# MCU_connector.net
KiCad netlist of a schematic drawn in Altium Designer
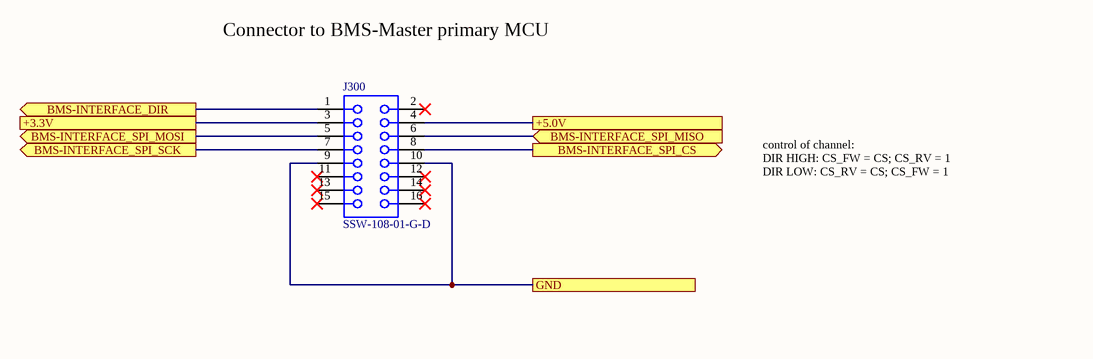
[diagram p0: MCU_connector.SchDoc]

(export (version "E")
  (design (tool "Eeschema 10.0.6"))
  (components
    (comp (ref "J300")
      (value "SSW-108-01-G-D")
      (footprint "SMTC-SSW-108-01-X-D")
      (description "SQ Post Socket, Through-hole, Vertical, -55 to 125 degC, 2.54mm Pitch, 16-Pin, Female, RoHS")
      (fields (field (name "MANUFACTURER") "Samtec"))
      (libsource (lib "Altium Content Vault") (part "SMTC-SSW-108-X-X-D-X"))
    )
  )
  (nets
    (net (code "1") (name "/+3.3V") (class "Default")
      (node (ref "J300") (pin "3") (pinfunction "3_3") (pintype "passive"))
    )
    (net (code "2") (name "/+5.0V") (class "Default")
      (node (ref "J300") (pin "4") (pinfunction "4_4") (pintype "passive"))
    )
    (net (code "3") (name "/BMS-INTERFACE_DIR") (class "Default")
      (node (ref "J300") (pin "1") (pinfunction "1_1") (pintype "passive"))
    )
    (net (code "4") (name "/BMS-INTERFACE_SPI_CS") (class "Default")
      (node (ref "J300") (pin "8") (pinfunction "8_8") (pintype "passive"))
    )
    (net (code "5") (name "/BMS-INTERFACE_SPI_MISO") (class "Default")
      (node (ref "J300") (pin "6") (pinfunction "6_6") (pintype "passive"))
    )
    (net (code "6") (name "/BMS-INTERFACE_SPI_MOSI") (class "Default")
      (node (ref "J300") (pin "5") (pinfunction "5_5") (pintype "passive"))
    )
    (net (code "7") (name "/BMS-INTERFACE_SPI_SCK") (class "Default")
      (node (ref "J300") (pin "7") (pinfunction "7_7") (pintype "passive"))
    )
    (net (code "8") (name "/GND") (class "Default")
      (node (ref "J300") (pin "10") (pinfunction "10_10") (pintype "passive"))
      (node (ref "J300") (pin "9") (pinfunction "9_9") (pintype "passive"))
    )
    (net (code "9") (name "unconnected-(J300-Pad2)") (class "Default")
      (node (ref "J300") (pin "2") (pinfunction "2_2") (pintype "passive+no_connect"))
    )
    (net (code "10") (name "unconnected-(J300-Pad11)") (class "Default")
      (node (ref "J300") (pin "11") (pinfunction "11_11") (pintype "passive+no_connect"))
    )
    (net (code "11") (name "unconnected-(J300-Pad12)") (class "Default")
      (node (ref "J300") (pin "12") (pinfunction "12_12") (pintype "passive+no_connect"))
    )
    (net (code "12") (name "unconnected-(J300-Pad13)") (class "Default")
      (node (ref "J300") (pin "13") (pinfunction "13_13") (pintype "passive+no_connect"))
    )
    (net (code "13") (name "unconnected-(J300-Pad14)") (class "Default")
      (node (ref "J300") (pin "14") (pinfunction "14_14") (pintype "passive+no_connect"))
    )
    (net (code "14") (name "unconnected-(J300-Pad15)") (class "Default")
      (node (ref "J300") (pin "15") (pinfunction "15_15") (pintype "passive+no_connect"))
    )
    (net (code "15") (name "unconnected-(J300-Pad16)") (class "Default")
      (node (ref "J300") (pin "16") (pinfunction "16_16") (pintype "passive+no_connect"))
    )
  )
)
